# shematic.net
KiCad netlist of a schematic drawn in EAGLE
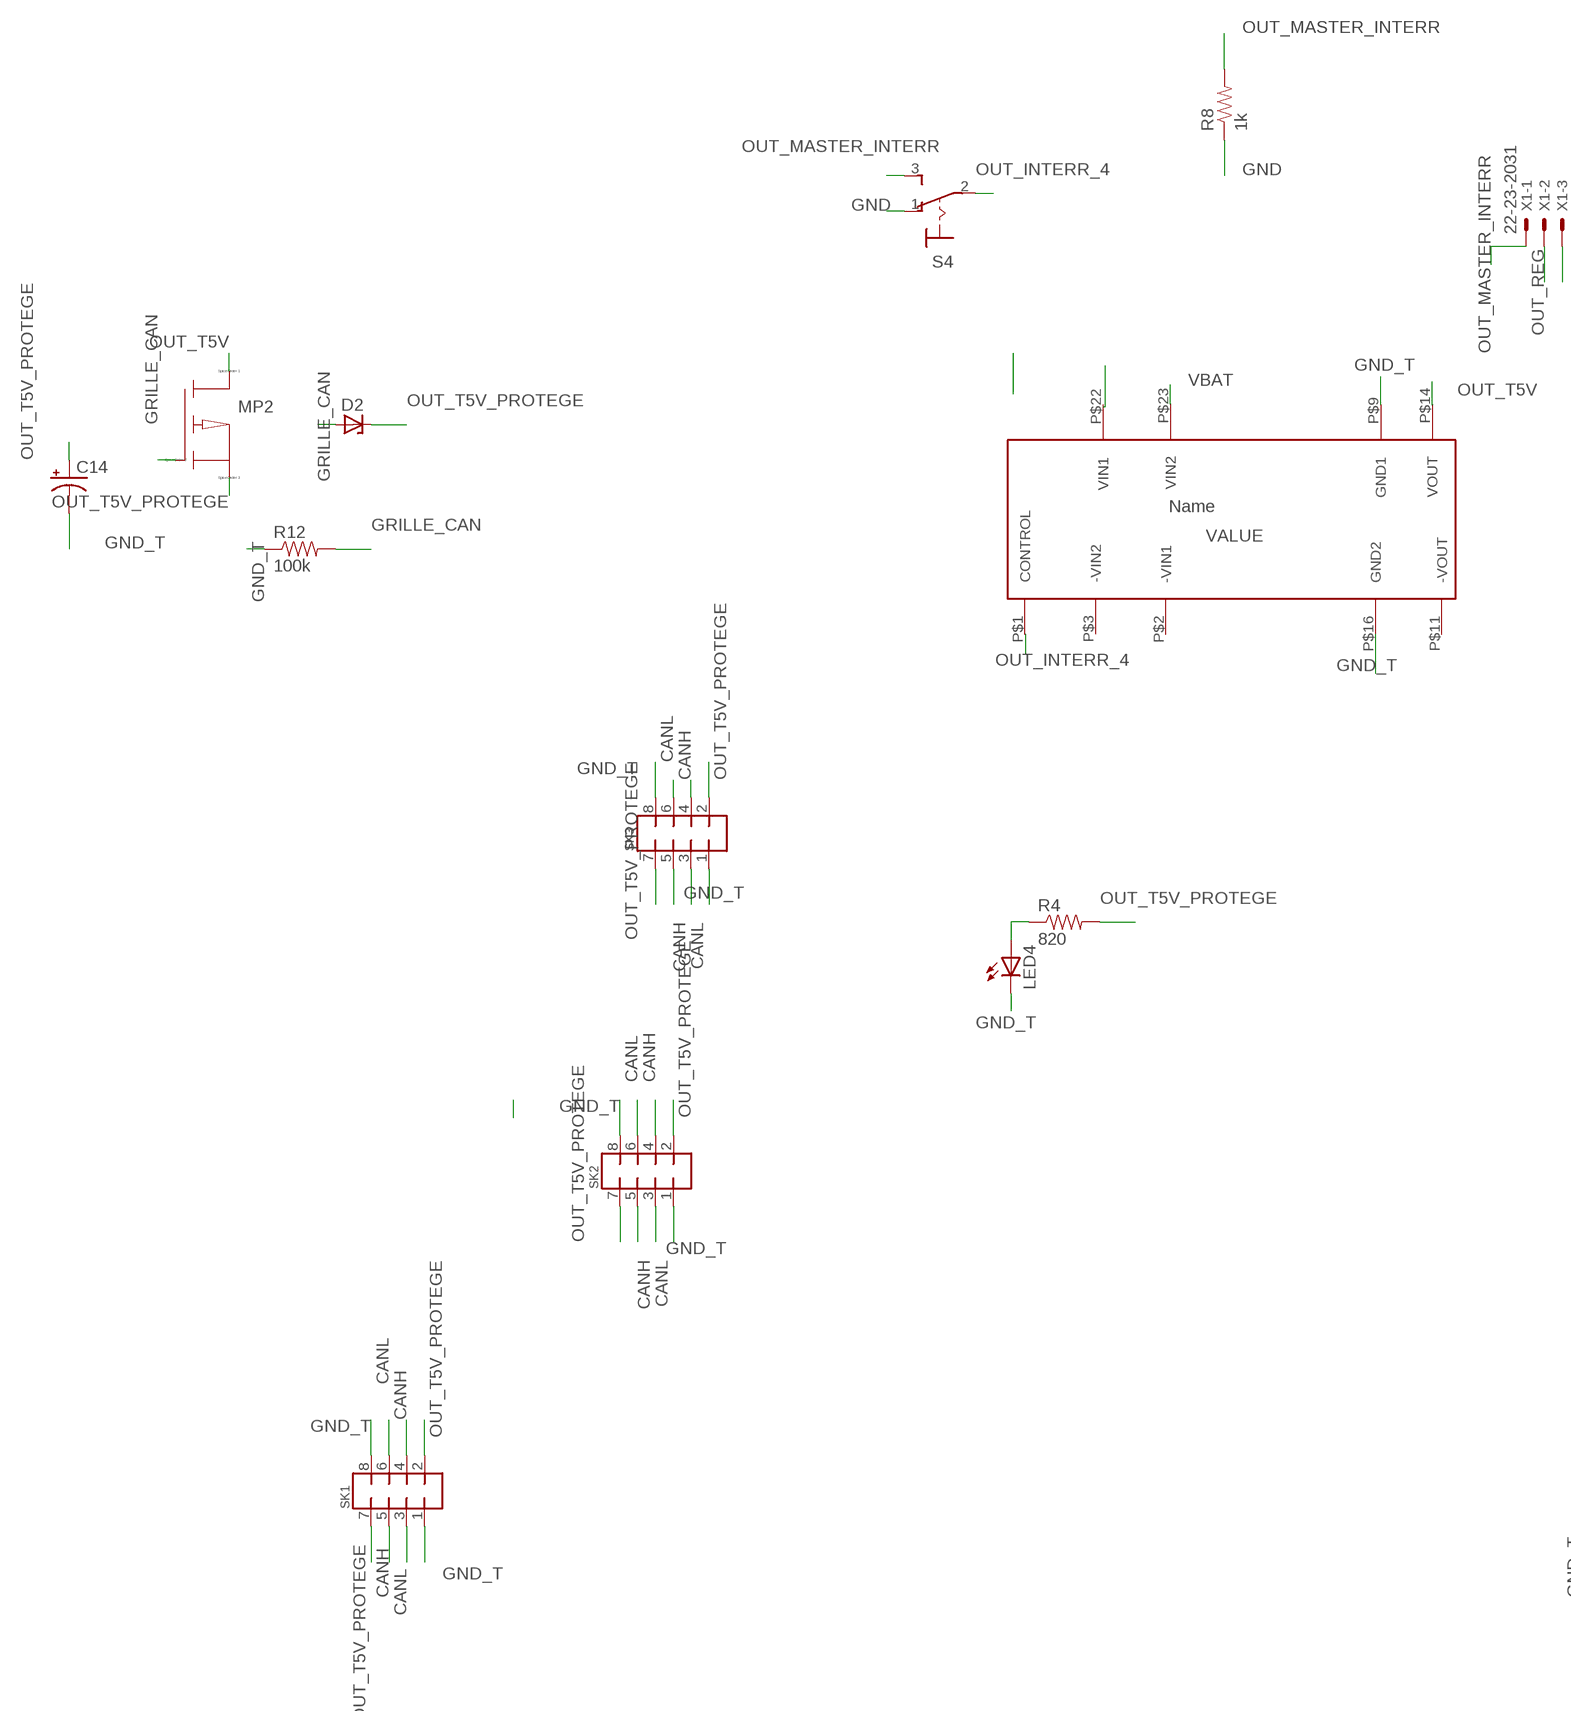
[diagram p0: schematic, sheet 1, part 1 of 2]
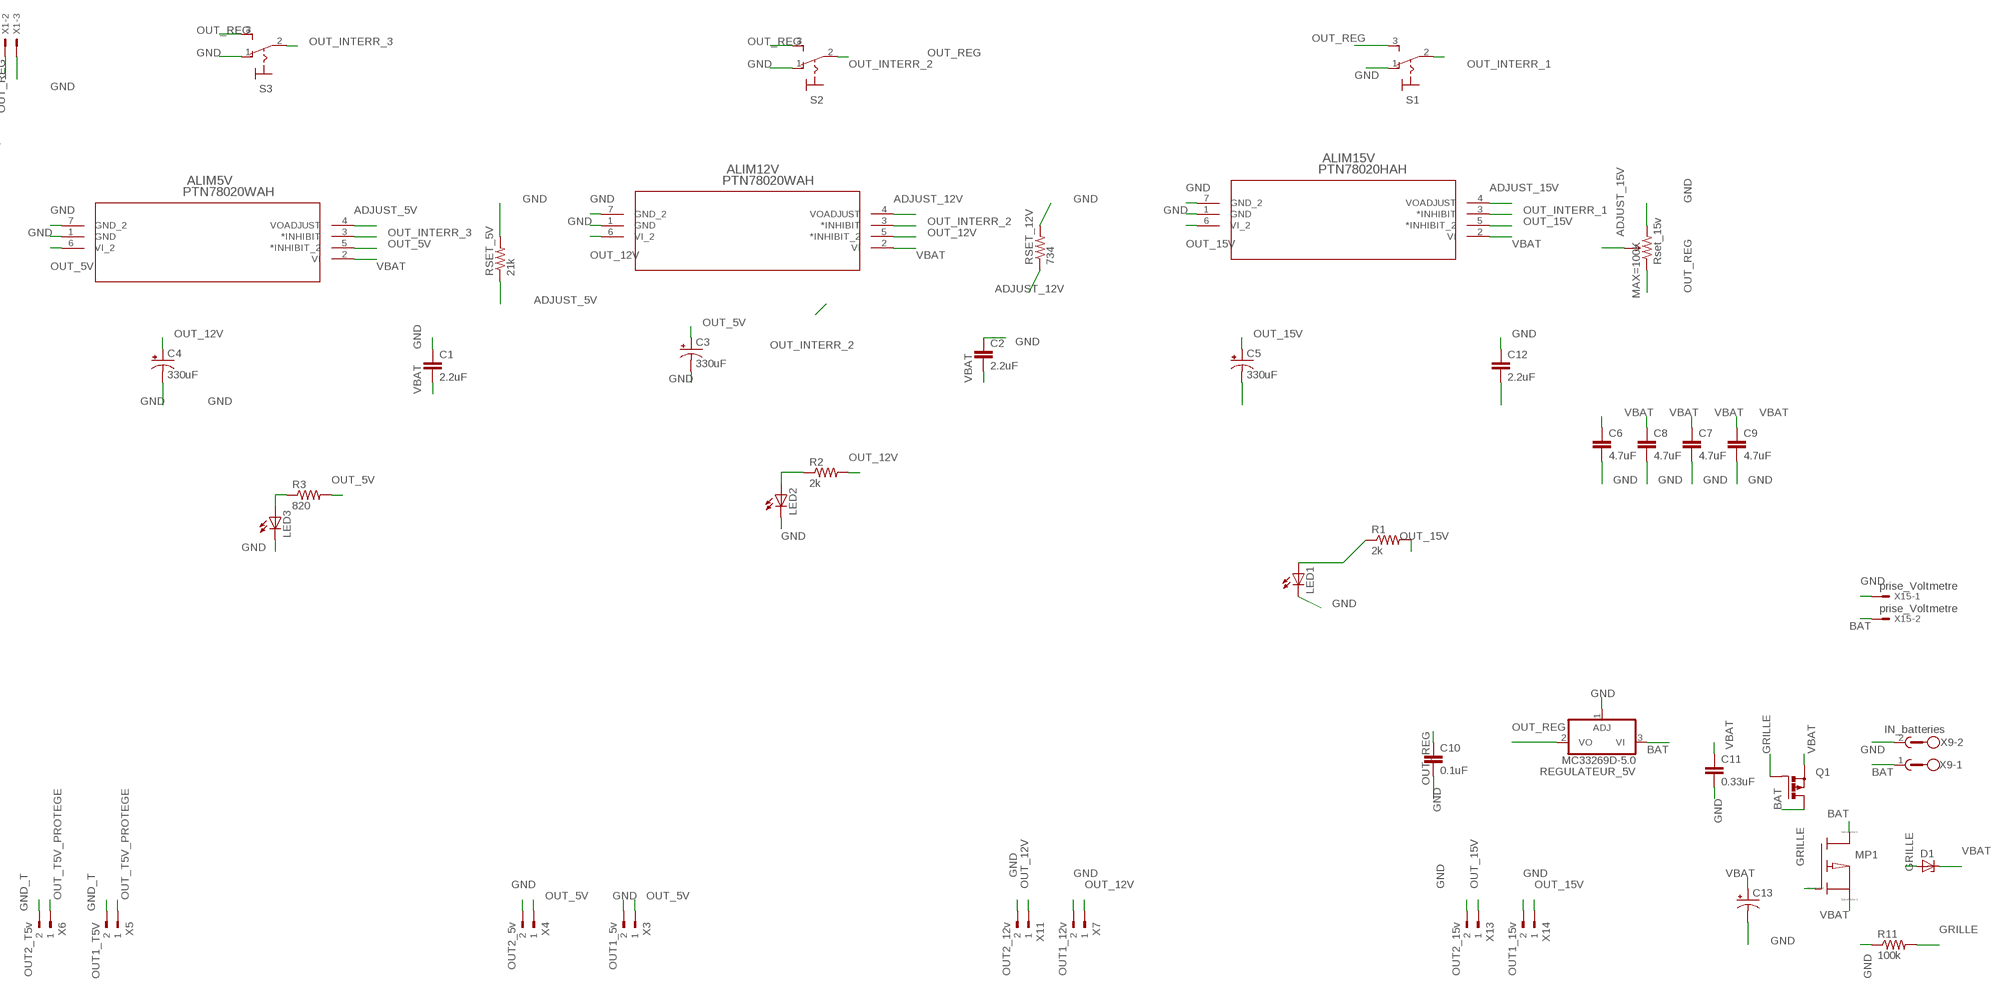
[diagram p1: schematic, sheet 1, part 2 of 2]

(export (version "E")
  (design (tool "Eeschema 10.0.6"))
  (components
    (comp (ref "ALIM5V")
      (value "PTN78020WAH")
      (footprint "eagle-import:EUK7")
      (libsource (lib "eagle-import") (part "PTN78020_"))
    )
    (comp (ref "ALIM12V")
      (value "PTN78020WAH")
      (footprint "eagle-import:EUK7")
      (libsource (lib "eagle-import") (part "PTN78020_"))
    )
    (comp (ref "ALIM15V")
      (value "PTN78020HAH")
      (footprint "eagle-import:EUK7")
      (libsource (lib "eagle-import") (part "PTN78020_"))
    )
    (comp (ref "C1")
      (value "2.2uF")
      (footprint "eagle-import:0805")
      (libsource (lib "eagle-import") (part "CAP0805"))
    )
    (comp (ref "C2")
      (value "2.2uF")
      (footprint "eagle-import:0805")
      (libsource (lib "eagle-import") (part "CAP0805"))
    )
    (comp (ref "C3")
      (value "330uF")
      (footprint "eagle-import:CPOL-RADIAL-100UF-25V")
      (libsource (lib "eagle-import") (part "CAP_POLPTH1"))
    )
    (comp (ref "C4")
      (value "330uF")
      (footprint "eagle-import:CPOL-RADIAL-100UF-25V")
      (libsource (lib "eagle-import") (part "CAP_POLPTH1"))
    )
    (comp (ref "C5")
      (value "330uF")
      (footprint "eagle-import:CPOL-RADIAL-100UF-25V")
      (libsource (lib "eagle-import") (part "CAP_POLPTH1"))
    )
    (comp (ref "C6")
      (value "4.7uF")
      (footprint "eagle-import:0805")
      (libsource (lib "eagle-import") (part "CAP0805"))
    )
    (comp (ref "C7")
      (value "4.7uF")
      (footprint "eagle-import:0805")
      (libsource (lib "eagle-import") (part "CAP0805"))
    )
    (comp (ref "C8")
      (value "4.7uF")
      (footprint "eagle-import:0805")
      (libsource (lib "eagle-import") (part "CAP0805"))
    )
    (comp (ref "C9")
      (value "4.7uF")
      (footprint "eagle-import:0805")
      (libsource (lib "eagle-import") (part "CAP0805"))
    )
    (comp (ref "C10")
      (value "0.1uF")
      (footprint "eagle-import:0805")
      (libsource (lib "eagle-import") (part "CAP0805"))
    )
    (comp (ref "C11")
      (value "0.33uF")
      (footprint "eagle-import:0805")
      (libsource (lib "eagle-import") (part "CAP0805"))
    )
    (comp (ref "C12")
      (value "2.2uF")
      (footprint "eagle-import:0805")
      (libsource (lib "eagle-import") (part "CAP0805"))
    )
    (comp (ref "C13")
      (value "CAP_POLPTH1")
      (footprint "eagle-import:CPOL-RADIAL-100UF-25V")
      (libsource (lib "eagle-import") (part "SparkFun-Passives_CAP_POLPTH1"))
    )
    (comp (ref "C14")
      (value "CAP_POLPTH1")
      (footprint "eagle-import:CPOL-RADIAL-100UF-25V")
      (libsource (lib "eagle-import") (part "SparkFun-Passives_CAP_POLPTH1"))
    )
    (comp (ref "D1")
      (value "ZENER-DIODESOT23")
      (footprint "eagle-import:SOT23")
      (libsource (lib "eagle-import") (part "ZENER-DIODESOT23"))
    )
    (comp (ref "D2")
      (value "ZENER-DIODESOT23")
      (footprint "eagle-import:SOT23")
      (libsource (lib "eagle-import") (part "ZENER-DIODESOT23"))
    )
    (comp (ref "LED1")
      (value "LEDCHIP-LED0805")
      (footprint "eagle-import:CHIP-LED0805")
      (libsource (lib "eagle-import") (part "LEDCHIP-LED0805"))
    )
    (comp (ref "LED2")
      (value "LEDCHIP-LED0805")
      (footprint "eagle-import:CHIP-LED0805")
      (libsource (lib "eagle-import") (part "LEDCHIP-LED0805"))
    )
    (comp (ref "LED3")
      (value "LEDCHIP-LED0805")
      (footprint "eagle-import:CHIP-LED0805")
      (libsource (lib "eagle-import") (part "LEDCHIP-LED0805"))
    )
    (comp (ref "LED4")
      (value "LEDCHIP-LED0805")
      (footprint "eagle-import:CHIP-LED0805")
      (libsource (lib "eagle-import") (part "LEDCHIP-LED0805"))
    )
    (comp (ref "MAX=100K")
      (value "Rset_15v")
      (footprint "eagle-import:3386U")
      (libsource (lib "eagle-import") (part "TRIMPOT-PTH-KNOB"))
    )
    (comp (ref "MP1")
      (value "PMOS")
      (footprint "eagle-import:SOT23")
      (libsource (lib "eagle-import") (part "PMOS"))
    )
    (comp (ref "MP2")
      (value "PMOS")
      (footprint "eagle-import:SOT23")
      (libsource (lib "eagle-import") (part "PMOS"))
    )
    (comp (ref "Q1")
      (value "PMOSFET_PTO220BH")
      (footprint "eagle-import:TO220BH")
      (libsource (lib "eagle-import") (part "PMOSFET_PTO220BH"))
    )
    (comp (ref "R1")
      (value "2k")
      (footprint "eagle-import:0805")
      (libsource (lib "eagle-import") (part "SparkFun-Resistors_RESISTOR0805-RES"))
    )
    (comp (ref "R2")
      (value "2k")
      (footprint "eagle-import:0805")
      (libsource (lib "eagle-import") (part "SparkFun-Resistors_RESISTOR0805-RES"))
    )
    (comp (ref "R3")
      (value "820")
      (footprint "eagle-import:0805")
      (libsource (lib "eagle-import") (part "SparkFun-Resistors_RESISTOR0805-RES"))
    )
    (comp (ref "R4")
      (value "820")
      (footprint "eagle-import:0805")
      (libsource (lib "eagle-import") (part "SparkFun-Resistors_RESISTOR0805-RES"))
    )
    (comp (ref "R8")
      (value "1k")
      (footprint "eagle-import:0805")
      (libsource (lib "eagle-import") (part "SparkFun-Resistors_RESISTOR0805-RES"))
    )
    (comp (ref "R11")
      (value "100k")
      (footprint "eagle-import:0805")
      (libsource (lib "eagle-import") (part "RESISTOR0805-RES"))
    )
    (comp (ref "R12")
      (value "100k")
      (footprint "eagle-import:0805")
      (libsource (lib "eagle-import") (part "RESISTOR0805-RES"))
    )
    (comp (ref "REGULATEUR_5V")
      (value "MC33269D-5.0")
      (footprint "eagle-import:DPACK")
      (libsource (lib "eagle-import") (part "MC33269?D-5.0"))
    )
    (comp (ref "RSET_5V")
      (value "21k")
      (footprint "eagle-import:0805")
      (libsource (lib "eagle-import") (part "RESISTOR0805-RES"))
    )
    (comp (ref "RSET_12V")
      (value "734")
      (footprint "eagle-import:0805")
      (libsource (lib "eagle-import") (part "RESISTOR0805-RES"))
    )
    (comp (ref "S1")
      (value "M9040P")
      (footprint "eagle-import:M9040P")
      (libsource (lib "eagle-import") (part "M9040P"))
    )
    (comp (ref "S2")
      (value "M9040P")
      (footprint "eagle-import:M9040P")
      (libsource (lib "eagle-import") (part "M9040P"))
    )
    (comp (ref "S3")
      (value "M9040P")
      (footprint "eagle-import:M9040P")
      (libsource (lib "eagle-import") (part "M9040P"))
    )
    (comp (ref "S4")
      (value "M9040P")
      (footprint "eagle-import:M9040P")
      (libsource (lib "eagle-import") (part "M9040P"))
    )
    (comp (ref "SK1")
      (value "MMATCH-8-PTH")
      (footprint "eagle-import:AMP-215079-8")
      (libsource (lib "eagle-import") (part "MMATCH-8-PTH"))
    )
    (comp (ref "SK2")
      (value "MMATCH-8-PTH")
      (footprint "eagle-import:AMP-215079-8")
      (libsource (lib "eagle-import") (part "MMATCH-8-PTH"))
    )
    (comp (ref "SK3")
      (value "MMATCH-8-PTH")
      (footprint "eagle-import:AMP-215079-8")
      (libsource (lib "eagle-import") (part "MMATCH-8-PTH"))
    )
    (comp (ref "U$1")
      (value "MURATA_NSC12")
      (footprint "eagle-import:MURATA_NSC12")
      (libsource (lib "eagle-import") (part "MURATA_NSC12"))
    )
    (comp (ref "X1")
      (value "22-23-2031")
      (footprint "eagle-import:22-23-2031")
      (fields (field (name "MF") "MOLEX"))
      (libsource (lib "eagle-import") (part "22-23-2031"))
    )
    (comp (ref "X3")
      (value "OUT1_5v")
      (footprint "eagle-import:90-2")
      (libsource (lib "eagle-import") (part "90-2"))
    )
    (comp (ref "X4")
      (value "OUT2_5v")
      (footprint "eagle-import:90-2")
      (libsource (lib "eagle-import") (part "90-2"))
    )
    (comp (ref "X5")
      (value "OUT1_T5V")
      (footprint "eagle-import:90-2")
      (libsource (lib "eagle-import") (part "90-2"))
    )
    (comp (ref "X6")
      (value "OUT2_T5v")
      (footprint "eagle-import:90-2")
      (libsource (lib "eagle-import") (part "90-2"))
    )
    (comp (ref "X7")
      (value "OUT1_12v")
      (footprint "eagle-import:90-2")
      (libsource (lib "eagle-import") (part "90-2"))
    )
    (comp (ref "X9")
      (value "IN_batteries")
      (footprint "eagle-import:GMSTBA2")
      (fields (field (name "MF") "FARNELL") (field (name "MPN") "1757242"))
      (libsource (lib "eagle-import") (part "GMSTBA2"))
    )
    (comp (ref "X11")
      (value "OUT2_12v")
      (footprint "eagle-import:90-2")
      (libsource (lib "eagle-import") (part "90-2"))
    )
    (comp (ref "X13")
      (value "OUT2_15v")
      (footprint "eagle-import:90-2")
      (libsource (lib "eagle-import") (part "90-2"))
    )
    (comp (ref "X14")
      (value "OUT1_15v")
      (footprint "eagle-import:90-2")
      (libsource (lib "eagle-import") (part "90-2"))
    )
    (comp (ref "X15")
      (value "prise_Voltmetre")
      (footprint "eagle-import:KK-156-2")
      (libsource (lib "eagle-import") (part "KK-156-2"))
    )
  )
  (nets
    (net (code "1") (name "/ADJUST_5V") (class "Default")
      (node (ref "ALIM5V") (pin "4") (pinfunction "VOADJUST_4") (pintype "passive"))
      (node (ref "RSET_5V") (pin "1") (pinfunction "1_1") (pintype "passive"))
    )
    (net (code "2") (name "/ADJUST_12V") (class "Default")
      (node (ref "ALIM12V") (pin "4") (pinfunction "VOADJUST_4") (pintype "passive"))
      (node (ref "RSET_12V") (pin "1") (pinfunction "1_1") (pintype "passive"))
    )
    (net (code "3") (name "/ADJUST_15V") (class "Default")
      (node (ref "ALIM15V") (pin "4") (pinfunction "VOADJUST_4") (pintype "passive"))
      (node (ref "MAX=100K") (pin "2") (pinfunction "WIPER_2") (pintype "passive"))
    )
    (net (code "4") (name "/BAT") (class "Default")
      (node (ref "MP1") (pin "3") (pinfunction "D_3") (pintype "passive"))
      (node (ref "Q1") (pin "D") (pinfunction "D_D") (pintype "passive"))
      (node (ref "REGULATEUR_5V") (pin "3") (pinfunction "VI_3") (pintype "input"))
      (node (ref "X15") (pin "2") (pinfunction "S_2") (pintype "passive"))
      (node (ref "X9") (pin "1") (pinfunction "1_1") (pintype "passive"))
    )
    (net (code "5") (name "/CANH") (class "Default")
      (node (ref "SK1") (pin "4") (pinfunction "4_4") (pintype "bidirectional"))
      (node (ref "SK1") (pin "5") (pinfunction "5_5") (pintype "bidirectional"))
      (node (ref "SK2") (pin "4") (pinfunction "4_4") (pintype "bidirectional"))
      (node (ref "SK2") (pin "5") (pinfunction "5_5") (pintype "bidirectional"))
      (node (ref "SK3") (pin "4") (pinfunction "4_4") (pintype "bidirectional"))
      (node (ref "SK3") (pin "5") (pinfunction "5_5") (pintype "bidirectional"))
    )
    (net (code "6") (name "/CANL") (class "Default")
      (node (ref "SK1") (pin "3") (pinfunction "3_3") (pintype "bidirectional"))
      (node (ref "SK1") (pin "6") (pinfunction "6_6") (pintype "bidirectional"))
      (node (ref "SK2") (pin "3") (pinfunction "3_3") (pintype "bidirectional"))
      (node (ref "SK2") (pin "6") (pinfunction "6_6") (pintype "bidirectional"))
      (node (ref "SK3") (pin "3") (pinfunction "3_3") (pintype "bidirectional"))
      (node (ref "SK3") (pin "6") (pinfunction "6_6") (pintype "bidirectional"))
    )
    (net (code "7") (name "/GND") (class "Default")
      (node (ref "ALIM12V") (pin "1") (pinfunction "GND_1") (pintype "passive"))
      (node (ref "ALIM12V") (pin "7") (pinfunction "GND_2_7") (pintype "passive"))
      (node (ref "ALIM15V") (pin "1") (pinfunction "GND_1") (pintype "passive"))
      (node (ref "ALIM15V") (pin "7") (pinfunction "GND_2_7") (pintype "passive"))
      (node (ref "ALIM5V") (pin "1") (pinfunction "GND_1") (pintype "passive"))
      (node (ref "ALIM5V") (pin "7") (pinfunction "GND_2_7") (pintype "passive"))
      (node (ref "C1") (pin "1") (pinfunction "1_1") (pintype "passive"))
      (node (ref "C10") (pin "2") (pinfunction "2_2") (pintype "passive"))
      (node (ref "C11") (pin "2") (pinfunction "2_2") (pintype "passive"))
      (node (ref "C12") (pin "1") (pinfunction "1_1") (pintype "passive"))
      (node (ref "C13") (pin "2") (pinfunction "-_2") (pintype "passive"))
      (node (ref "C2") (pin "1") (pinfunction "1_1") (pintype "passive"))
      (node (ref "C3") (pin "2") (pinfunction "-_2") (pintype "passive"))
      (node (ref "C4") (pin "2") (pinfunction "-_2") (pintype "passive"))
      (node (ref "C5") (pin "2") (pinfunction "-_2") (pintype "passive"))
      (node (ref "C6") (pin "2") (pinfunction "2_2") (pintype "passive"))
      (node (ref "C7") (pin "2") (pinfunction "2_2") (pintype "passive"))
      (node (ref "C8") (pin "2") (pinfunction "2_2") (pintype "passive"))
      (node (ref "C9") (pin "2") (pinfunction "2_2") (pintype "passive"))
      (node (ref "LED1") (pin "C") (pinfunction "C_C") (pintype "passive"))
      (node (ref "LED2") (pin "C") (pinfunction "C_C") (pintype "passive"))
      (node (ref "LED3") (pin "C") (pinfunction "C_C") (pintype "passive"))
      (node (ref "MAX=100K") (pin "3") (pinfunction "CW_3") (pintype "passive"))
      (node (ref "R11") (pin "1") (pinfunction "1_1") (pintype "passive"))
      (node (ref "R8") (pin "1") (pinfunction "1_1") (pintype "passive"))
      (node (ref "REGULATEUR_5V") (pin "1") (pinfunction "ADJ_1") (pintype "input"))
      (node (ref "RSET_12V") (pin "2") (pinfunction "2_2") (pintype "passive"))
      (node (ref "RSET_5V") (pin "2") (pinfunction "2_2") (pintype "passive"))
      (node (ref "S1") (pin "1") (pinfunction "O_1") (pintype "passive"))
      (node (ref "S2") (pin "1") (pinfunction "O_1") (pintype "passive"))
      (node (ref "S3") (pin "1") (pinfunction "O_1") (pintype "passive"))
      (node (ref "S4") (pin "1") (pinfunction "O_1") (pintype "passive"))
      (node (ref "X1") (pin "3") (pinfunction "S_3") (pintype "passive"))
      (node (ref "X11") (pin "2") (pinfunction "2_2") (pintype "passive"))
      (node (ref "X13") (pin "2") (pinfunction "2_2") (pintype "passive"))
      (node (ref "X14") (pin "2") (pinfunction "2_2") (pintype "passive"))
      (node (ref "X15") (pin "1") (pinfunction "S_1") (pintype "passive"))
      (node (ref "X3") (pin "2") (pinfunction "2_2") (pintype "passive"))
      (node (ref "X4") (pin "2") (pinfunction "2_2") (pintype "passive"))
      (node (ref "X7") (pin "2") (pinfunction "2_2") (pintype "passive"))
      (node (ref "X9") (pin "2") (pinfunction "1_2") (pintype "passive"))
    )
    (net (code "8") (name "/GND_T") (class "Default")
      (node (ref "C14") (pin "2") (pinfunction "-_2") (pintype "passive"))
      (node (ref "LED4") (pin "C") (pinfunction "C_C") (pintype "passive"))
      (node (ref "R12") (pin "1") (pinfunction "1_1") (pintype "passive"))
      (node (ref "SK1") (pin "1") (pinfunction "1_1") (pintype "bidirectional"))
      (node (ref "SK1") (pin "8") (pinfunction "8_8") (pintype "bidirectional"))
      (node (ref "SK2") (pin "1") (pinfunction "1_1") (pintype "bidirectional"))
      (node (ref "SK2") (pin "8") (pinfunction "8_8") (pintype "bidirectional"))
      (node (ref "SK3") (pin "1") (pinfunction "1_1") (pintype "bidirectional"))
      (node (ref "SK3") (pin "8") (pinfunction "8_8") (pintype "bidirectional"))
      (node (ref "X5") (pin "2") (pinfunction "2_2") (pintype "passive"))
      (node (ref "X6") (pin "2") (pinfunction "2_2") (pintype "passive"))
    )
    (net (code "9") (name "/GRILLE") (class "Default")
      (node (ref "D1") (pin "1") (pinfunction "A_1") (pintype "passive"))
      (node (ref "MP1") (pin "1") (pinfunction "G_1") (pintype "passive"))
      (node (ref "Q1") (pin "G") (pinfunction "G_G") (pintype "passive"))
      (node (ref "R11") (pin "2") (pinfunction "2_2") (pintype "passive"))
    )
    (net (code "10") (name "/GRILLE_CAN") (class "Default")
      (node (ref "D2") (pin "1") (pinfunction "A_1") (pintype "passive"))
      (node (ref "MP2") (pin "1") (pinfunction "G_1") (pintype "passive"))
      (node (ref "R12") (pin "2") (pinfunction "2_2") (pintype "passive"))
    )
    (net (code "11") (name "/OUT_5V") (class "Default")
      (node (ref "ALIM5V") (pin "5") (pinfunction "*INHIBIT_2_5") (pintype "passive"))
      (node (ref "ALIM5V") (pin "6") (pinfunction "VI_2_6") (pintype "passive"))
      (node (ref "C3") (pin "1") (pinfunction "+_1") (pintype "passive"))
      (node (ref "R3") (pin "2") (pinfunction "2_2") (pintype "passive"))
      (node (ref "X3") (pin "1") (pinfunction "1_1") (pintype "passive"))
      (node (ref "X4") (pin "1") (pinfunction "1_1") (pintype "passive"))
    )
    (net (code "12") (name "/OUT_12V") (class "Default")
      (node (ref "ALIM12V") (pin "5") (pinfunction "*INHIBIT_2_5") (pintype "passive"))
      (node (ref "ALIM12V") (pin "6") (pinfunction "VI_2_6") (pintype "passive"))
      (node (ref "C4") (pin "1") (pinfunction "+_1") (pintype "passive"))
      (node (ref "R2") (pin "2") (pinfunction "2_2") (pintype "passive"))
      (node (ref "X11") (pin "1") (pinfunction "1_1") (pintype "passive"))
      (node (ref "X7") (pin "1") (pinfunction "1_1") (pintype "passive"))
    )
    (net (code "13") (name "/OUT_15V") (class "Default")
      (node (ref "ALIM15V") (pin "5") (pinfunction "*INHIBIT_2_5") (pintype "passive"))
      (node (ref "ALIM15V") (pin "6") (pinfunction "VI_2_6") (pintype "passive"))
      (node (ref "C5") (pin "1") (pinfunction "+_1") (pintype "passive"))
      (node (ref "R1") (pin "2") (pinfunction "2_2") (pintype "passive"))
      (node (ref "X13") (pin "1") (pinfunction "1_1") (pintype "passive"))
      (node (ref "X14") (pin "1") (pinfunction "1_1") (pintype "passive"))
    )
    (net (code "14") (name "/OUT_INTERR_1") (class "Default")
      (node (ref "ALIM15V") (pin "3") (pinfunction "*INHIBIT_3") (pintype "passive"))
      (node (ref "S1") (pin "2") (pinfunction "P_2") (pintype "passive"))
    )
    (net (code "15") (name "/OUT_INTERR_2") (class "Default")
      (node (ref "ALIM12V") (pin "3") (pinfunction "*INHIBIT_3") (pintype "passive"))
      (node (ref "S2") (pin "2") (pinfunction "P_2") (pintype "passive"))
    )
    (net (code "16") (name "/OUT_INTERR_3") (class "Default")
      (node (ref "ALIM5V") (pin "3") (pinfunction "*INHIBIT_3") (pintype "passive"))
      (node (ref "S3") (pin "2") (pinfunction "P_2") (pintype "passive"))
    )
    (net (code "17") (name "/OUT_INTERR_4") (class "Default")
      (node (ref "S4") (pin "2") (pinfunction "P_2") (pintype "passive"))
    )
    (net (code "18") (name "/OUT_MASTER_INTERR") (class "Default")
      (node (ref "R8") (pin "2") (pinfunction "2_2") (pintype "passive"))
      (node (ref "S4") (pin "3") (pinfunction "S_3") (pintype "passive"))
      (node (ref "X1") (pin "1") (pinfunction "S_1") (pintype "passive"))
    )
    (net (code "19") (name "/OUT_REG") (class "Default")
      (node (ref "C10") (pin "1") (pinfunction "1_1") (pintype "passive"))
      (node (ref "MAX=100K") (pin "1") (pinfunction "CCW_1") (pintype "passive"))
      (node (ref "REGULATEUR_5V") (pin "2") (pinfunction "VO_2") (pintype "passive"))
      (node (ref "S1") (pin "3") (pinfunction "S_3") (pintype "passive"))
      (node (ref "S2") (pin "3") (pinfunction "S_3") (pintype "passive"))
      (node (ref "S3") (pin "3") (pinfunction "S_3") (pintype "passive"))
      (node (ref "X1") (pin "2") (pinfunction "S_2") (pintype "passive"))
    )
    (net (code "20") (name "/OUT_T5V") (class "Default")
      (node (ref "MP2") (pin "3") (pinfunction "D_3") (pintype "passive"))
    )
    (net (code "21") (name "/OUT_T5V_PROTEGE") (class "Default")
      (node (ref "C14") (pin "1") (pinfunction "+_1") (pintype "passive"))
      (node (ref "D2") (pin "3") (pinfunction "C_3") (pintype "passive"))
      (node (ref "MP2") (pin "2") (pinfunction "S_2") (pintype "passive"))
      (node (ref "R4") (pin "2") (pinfunction "2_2") (pintype "passive"))
      (node (ref "SK1") (pin "2") (pinfunction "2_2") (pintype "bidirectional"))
      (node (ref "SK1") (pin "7") (pinfunction "7_7") (pintype "bidirectional"))
      (node (ref "SK2") (pin "2") (pinfunction "2_2") (pintype "bidirectional"))
      (node (ref "SK2") (pin "7") (pinfunction "7_7") (pintype "bidirectional"))
      (node (ref "SK3") (pin "2") (pinfunction "2_2") (pintype "bidirectional"))
      (node (ref "SK3") (pin "7") (pinfunction "7_7") (pintype "bidirectional"))
      (node (ref "X5") (pin "1") (pinfunction "1_1") (pintype "passive"))
      (node (ref "X6") (pin "1") (pinfunction "1_1") (pintype "passive"))
    )
    (net (code "22") (name "/VBAT") (class "Default")
      (node (ref "ALIM12V") (pin "2") (pinfunction "VI_2") (pintype "passive"))
      (node (ref "ALIM15V") (pin "2") (pinfunction "VI_2") (pintype "passive"))
      (node (ref "ALIM5V") (pin "2") (pinfunction "VI_2") (pintype "passive"))
      (node (ref "C1") (pin "2") (pinfunction "2_2") (pintype "passive"))
      (node (ref "C11") (pin "1") (pinfunction "1_1") (pintype "passive"))
      (node (ref "C12") (pin "2") (pinfunction "2_2") (pintype "passive"))
      (node (ref "C13") (pin "1") (pinfunction "+_1") (pintype "passive"))
      (node (ref "C2") (pin "2") (pinfunction "2_2") (pintype "passive"))
      (node (ref "C6") (pin "1") (pinfunction "1_1") (pintype "passive"))
      (node (ref "C7") (pin "1") (pinfunction "1_1") (pintype "passive"))
      (node (ref "C8") (pin "1") (pinfunction "1_1") (pintype "passive"))
      (node (ref "C9") (pin "1") (pinfunction "1_1") (pintype "passive"))
      (node (ref "D1") (pin "3") (pinfunction "C_3") (pintype "passive"))
      (node (ref "MP1") (pin "2") (pinfunction "S_2") (pintype "passive"))
      (node (ref "Q1") (pin "S") (pinfunction "S_S") (pintype "passive"))
    )
    (net (code "23") (name "Net-(LED1-PadA)") (class "Default")
      (node (ref "LED1") (pin "A") (pinfunction "A_A") (pintype "passive"))
      (node (ref "R1") (pin "1") (pinfunction "1_1") (pintype "passive"))
    )
    (net (code "24") (name "Net-(LED2-PadA)") (class "Default")
      (node (ref "LED2") (pin "A") (pinfunction "A_A") (pintype "passive"))
      (node (ref "R2") (pin "1") (pinfunction "1_1") (pintype "passive"))
    )
    (net (code "25") (name "Net-(LED3-PadA)") (class "Default")
      (node (ref "LED3") (pin "A") (pinfunction "A_A") (pintype "passive"))
      (node (ref "R3") (pin "1") (pinfunction "1_1") (pintype "passive"))
    )
    (net (code "26") (name "Net-(LED4-PadA)") (class "Default")
      (node (ref "LED4") (pin "A") (pinfunction "A_A") (pintype "passive"))
      (node (ref "R4") (pin "1") (pinfunction "1_1") (pintype "passive"))
    )
    (net (code "27") (name "unconnected-(U$1--VIN1-PadP$2)") (class "Default")
      (node (ref "U$1") (pin "P$2") (pinfunction "-VIN1_P$2") (pintype "bidirectional"))
    )
    (net (code "28") (name "unconnected-(U$1--VIN2-PadP$3)") (class "Default")
      (node (ref "U$1") (pin "P$3") (pinfunction "-VIN2_P$3") (pintype "bidirectional"))
    )
    (net (code "29") (name "unconnected-(U$1--VOUT-PadP$11)") (class "Default")
      (node (ref "U$1") (pin "P$11") (pinfunction "-VOUT_P$11") (pintype "bidirectional"))
    )
    (net (code "30") (name "unconnected-(U$1-CONTROL-PadP$1)") (class "Default")
      (node (ref "U$1") (pin "P$1") (pinfunction "CONTROL_P$1") (pintype "bidirectional"))
    )
    (net (code "31") (name "unconnected-(U$1-GND1-PadP$9)") (class "Default")
      (node (ref "U$1") (pin "P$9") (pinfunction "GND1_P$9") (pintype "bidirectional"))
    )
    (net (code "32") (name "unconnected-(U$1-GND2-PadP$16)") (class "Default")
      (node (ref "U$1") (pin "P$16") (pinfunction "GND2_P$16") (pintype "bidirectional"))
    )
    (net (code "33") (name "unconnected-(U$1-VIN1-PadP$22)") (class "Default")
      (node (ref "U$1") (pin "P$22") (pinfunction "VIN1_P$22") (pintype "bidirectional"))
    )
    (net (code "34") (name "unconnected-(U$1-VIN2-PadP$23)") (class "Default")
      (node (ref "U$1") (pin "P$23") (pinfunction "VIN2_P$23") (pintype "bidirectional"))
    )
    (net (code "35") (name "unconnected-(U$1-VOUT-PadP$14)") (class "Default")
      (node (ref "U$1") (pin "P$14") (pinfunction "VOUT_P$14") (pintype "bidirectional"))
    )
  )
)
